# RaspberryPiSigfoxBoard.net
KiCad netlist of a schematic drawn in EAGLE
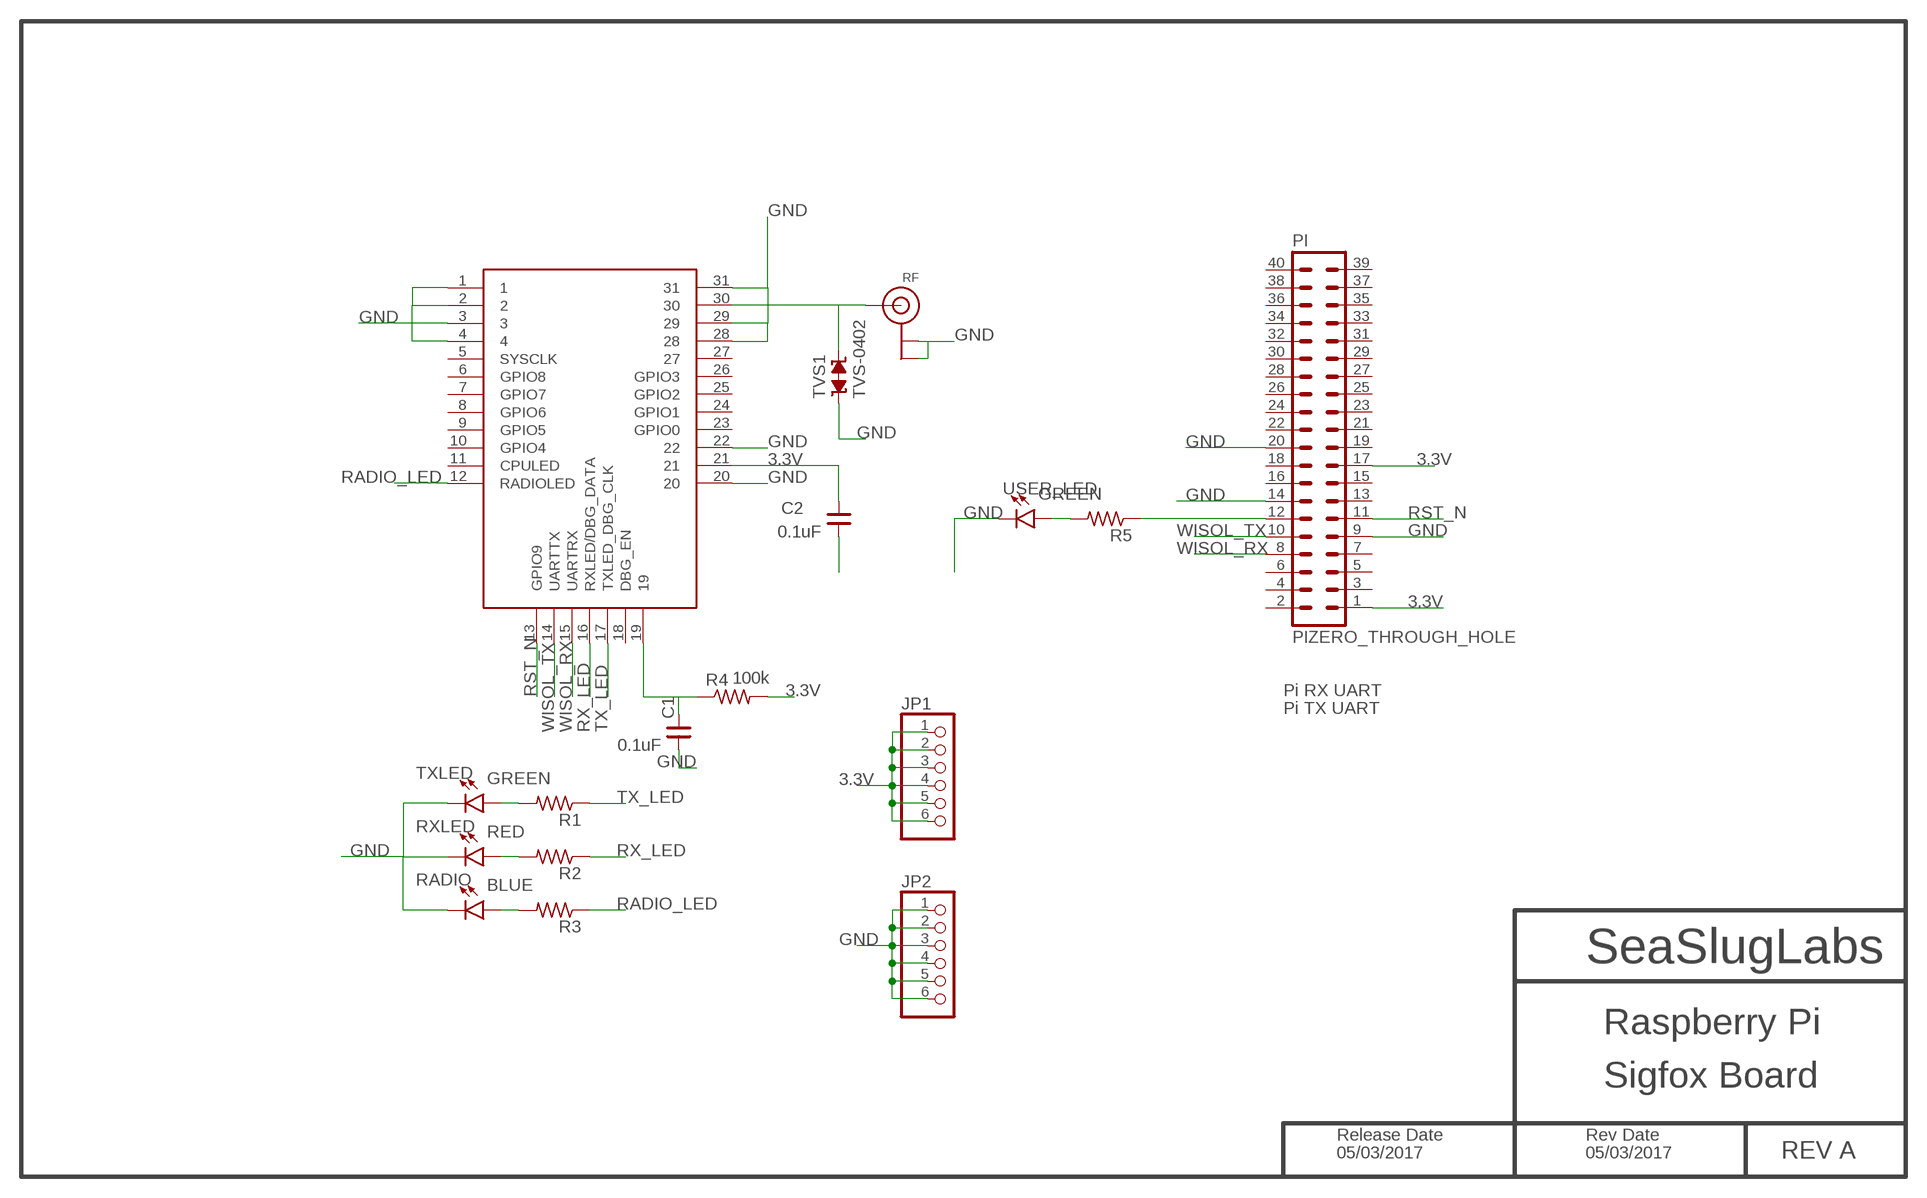
[diagram p0: schematic, sheet 1]

(export (version "E")
  (design (tool "Eeschema 10.0.6"))
  (components
    (comp (ref "C1")
      (value "0.1uF")
      (footprint "eagle-import:0402")
      (libsource (lib "eagle-import") (part "CNP-0402"))
    )
    (comp (ref "C2")
      (value "0.1uF")
      (footprint "eagle-import:0402")
      (libsource (lib "eagle-import") (part "CNP-0402"))
    )
    (comp (ref "JP1")
      (value "PINHD-1X6B")
      (footprint "eagle-import:1X06-BIG")
      (libsource (lib "eagle-import") (part "PINHD-1X6B"))
    )
    (comp (ref "JP2")
      (value "PINHD-1X6B")
      (footprint "eagle-import:1X06-BIG")
      (libsource (lib "eagle-import") (part "PINHD-1X6B"))
    )
    (comp (ref "PI")
      (value "PIZERO_THROUGH_HOLE")
      (footprint "eagle-import:PIZERO_THOUGH_HOLE")
      (libsource (lib "eagle-import") (part "PIZERO_THROUGH_HOLE"))
    )
    (comp (ref "R1")
      (value "R-US_R0402")
      (footprint "eagle-import:R0402")
      (libsource (lib "eagle-import") (part "R-US_R0402"))
    )
    (comp (ref "R2")
      (value "R-US_R0402")
      (footprint "eagle-import:R0402")
      (libsource (lib "eagle-import") (part "R-US_R0402"))
    )
    (comp (ref "R3")
      (value "R-US_R0402")
      (footprint "eagle-import:R0402")
      (libsource (lib "eagle-import") (part "R-US_R0402"))
    )
    (comp (ref "R4")
      (value "100k")
      (footprint "eagle-import:R0402")
      (libsource (lib "eagle-import") (part "R-US_R0402"))
    )
    (comp (ref "R5")
      (value "R-US_R0402")
      (footprint "eagle-import:R0402")
      (libsource (lib "eagle-import") (part "R-US_R0402"))
    )
    (comp (ref "RADIO")
      (value "BLUE")
      (footprint "eagle-import:LED-0603")
      (libsource (lib "eagle-import") (part "LED-BLUE0603"))
    )
    (comp (ref "RF")
      (value "ANTENNA_U.FL")
      (footprint "eagle-import:U.FL")
      (libsource (lib "eagle-import") (part "ANTENNA_U.FL"))
    )
    (comp (ref "RXLED")
      (value "RED")
      (footprint "eagle-import:LED-0603")
      (libsource (lib "eagle-import") (part "LED-RED0603"))
    )
    (comp (ref "TVS1")
      (value "TVS-0402")
      (footprint "eagle-import:TVS0402")
      (libsource (lib "eagle-import") (part "TVS-0402"))
    )
    (comp (ref "TXLED")
      (value "GREEN")
      (footprint "eagle-import:LED-0603")
      (libsource (lib "eagle-import") (part "LED-GREEN0603"))
    )
    (comp (ref "USER_LED")
      (value "GREEN")
      (footprint "eagle-import:LED-0603")
      (libsource (lib "eagle-import") (part "LED-GREEN0603"))
    )
    (comp (ref "WSSFM10R2")
      (value "WSSFM10R2/R4WSSFM10R2R4")
      (footprint "eagle-import:WISOL")
      (libsource (lib "eagle-import") (part "WSSFM10R2/R4WSSFM10R2R4"))
    )
  )
  (nets
    (net (code "1") (name "/3.3V") (class "Default")
      (node (ref "C2") (pin "2") (pinfunction "2_2") (pintype "passive"))
      (node (ref "JP1") (pin "1") (pinfunction "1_1") (pintype "passive"))
      (node (ref "JP1") (pin "2") (pinfunction "2_2") (pintype "passive"))
      (node (ref "JP1") (pin "3") (pinfunction "3_3") (pintype "passive"))
      (node (ref "JP1") (pin "4") (pinfunction "4_4") (pintype "passive"))
      (node (ref "JP1") (pin "5") (pinfunction "5_5") (pintype "passive"))
      (node (ref "JP1") (pin "6") (pinfunction "6_6") (pintype "passive"))
      (node (ref "PI") (pin "1") (pinfunction "1_1") (pintype "passive"))
      (node (ref "PI") (pin "17") (pinfunction "17_17") (pintype "passive"))
      (node (ref "R4") (pin "2") (pinfunction "2_2") (pintype "passive"))
      (node (ref "WSSFM10R2") (pin "21") (pinfunction "21_21") (pintype "bidirectional"))
    )
    (net (code "2") (name "/GND") (class "Default")
      (node (ref "C1") (pin "1") (pinfunction "1_1") (pintype "passive"))
      (node (ref "C2") (pin "1") (pinfunction "1_1") (pintype "passive"))
      (node (ref "JP2") (pin "1") (pinfunction "1_1") (pintype "passive"))
      (node (ref "JP2") (pin "2") (pinfunction "2_2") (pintype "passive"))
      (node (ref "JP2") (pin "3") (pinfunction "3_3") (pintype "passive"))
      (node (ref "JP2") (pin "4") (pinfunction "4_4") (pintype "passive"))
      (node (ref "JP2") (pin "5") (pinfunction "5_5") (pintype "passive"))
      (node (ref "JP2") (pin "6") (pinfunction "6_6") (pintype "passive"))
      (node (ref "PI") (pin "14") (pinfunction "14_14") (pintype "passive"))
      (node (ref "PI") (pin "20") (pinfunction "20_20") (pintype "passive"))
      (node (ref "PI") (pin "9") (pinfunction "9_9") (pintype "passive"))
      (node (ref "RADIO") (pin "C") (pinfunction "C_C") (pintype "passive"))
      (node (ref "RF") (pin "1") (pinfunction "GND_1") (pintype "passive"))
      (node (ref "RF") (pin "2") (pinfunction "GND_2") (pintype "passive"))
      (node (ref "RXLED") (pin "C") (pinfunction "C_C") (pintype "passive"))
      (node (ref "TVS1") (pin "1") (pinfunction "1_1") (pintype "passive"))
      (node (ref "TXLED") (pin "C") (pinfunction "C_C") (pintype "passive"))
      (node (ref "USER_LED") (pin "C") (pinfunction "C_C") (pintype "passive"))
      (node (ref "WSSFM10R2") (pin "1") (pinfunction "1_1") (pintype "bidirectional"))
      (node (ref "WSSFM10R2") (pin "2") (pinfunction "2_2") (pintype "bidirectional"))
      (node (ref "WSSFM10R2") (pin "20") (pinfunction "20_20") (pintype "bidirectional"))
      (node (ref "WSSFM10R2") (pin "22") (pinfunction "22_22") (pintype "bidirectional"))
      (node (ref "WSSFM10R2") (pin "28") (pinfunction "28_28") (pintype "bidirectional"))
      (node (ref "WSSFM10R2") (pin "29") (pinfunction "29_29") (pintype "bidirectional"))
      (node (ref "WSSFM10R2") (pin "3") (pinfunction "3_3") (pintype "bidirectional"))
      (node (ref "WSSFM10R2") (pin "31") (pinfunction "31_31") (pintype "bidirectional"))
      (node (ref "WSSFM10R2") (pin "4") (pinfunction "4_4") (pintype "bidirectional"))
    )
    (net (code "3") (name "/RADIO_LED") (class "Default")
      (node (ref "R3") (pin "1") (pinfunction "1_1") (pintype "passive"))
      (node (ref "WSSFM10R2") (pin "12") (pinfunction "RADIOLED_12") (pintype "bidirectional"))
    )
    (net (code "4") (name "/RST_N") (class "Default")
      (node (ref "PI") (pin "11") (pinfunction "11_11") (pintype "passive"))
      (node (ref "WSSFM10R2") (pin "13") (pinfunction "GPIO9_13") (pintype "bidirectional"))
    )
    (net (code "5") (name "/RX_LED") (class "Default")
      (node (ref "R2") (pin "1") (pinfunction "1_1") (pintype "passive"))
      (node (ref "WSSFM10R2") (pin "16") (pinfunction "RXLED/DBG_DATA_16") (pintype "bidirectional"))
    )
    (net (code "6") (name "/TX_LED") (class "Default")
      (node (ref "R1") (pin "1") (pinfunction "1_1") (pintype "passive"))
      (node (ref "WSSFM10R2") (pin "17") (pinfunction "TXLED_DBG_CLK_17") (pintype "bidirectional"))
    )
    (net (code "7") (name "/WISOL_RX") (class "Default")
      (node (ref "PI") (pin "8") (pinfunction "8_8") (pintype "passive"))
      (node (ref "WSSFM10R2") (pin "15") (pinfunction "UARTRX_15") (pintype "bidirectional"))
    )
    (net (code "8") (name "/WISOL_TX") (class "Default")
      (node (ref "PI") (pin "10") (pinfunction "10_10") (pintype "passive"))
      (node (ref "WSSFM10R2") (pin "14") (pinfunction "UARTTX_14") (pintype "bidirectional"))
    )
    (net (code "9") (name "Net-(C1-Pad2)") (class "Default")
      (node (ref "C1") (pin "2") (pinfunction "2_2") (pintype "passive"))
      (node (ref "R4") (pin "1") (pinfunction "1_1") (pintype "passive"))
      (node (ref "WSSFM10R2") (pin "19") (pinfunction "19_19") (pintype "bidirectional"))
    )
    (net (code "10") (name "Net-(PI-Pad12)") (class "Default")
      (node (ref "PI") (pin "12") (pinfunction "12_12") (pintype "passive"))
      (node (ref "R5") (pin "1") (pinfunction "1_1") (pintype "passive"))
    )
    (net (code "11") (name "Net-(R1-Pad2)") (class "Default")
      (node (ref "R1") (pin "2") (pinfunction "2_2") (pintype "passive"))
      (node (ref "TXLED") (pin "A") (pinfunction "A_A") (pintype "passive"))
    )
    (net (code "12") (name "Net-(R2-Pad2)") (class "Default")
      (node (ref "R2") (pin "2") (pinfunction "2_2") (pintype "passive"))
      (node (ref "RXLED") (pin "A") (pinfunction "A_A") (pintype "passive"))
    )
    (net (code "13") (name "Net-(R3-Pad2)") (class "Default")
      (node (ref "R3") (pin "2") (pinfunction "2_2") (pintype "passive"))
      (node (ref "RADIO") (pin "A") (pinfunction "A_A") (pintype "passive"))
    )
    (net (code "14") (name "Net-(R5-Pad2)") (class "Default")
      (node (ref "R5") (pin "2") (pinfunction "2_2") (pintype "passive"))
      (node (ref "USER_LED") (pin "A") (pinfunction "A_A") (pintype "passive"))
    )
    (net (code "15") (name "Net-(RF-SIGNAL)") (class "Default")
      (node (ref "RF") (pin "3") (pinfunction "SIGNAL_3") (pintype "passive"))
      (node (ref "TVS1") (pin "2") (pinfunction "2_2") (pintype "passive"))
      (node (ref "WSSFM10R2") (pin "30") (pinfunction "30_30") (pintype "bidirectional"))
    )
    (net (code "16") (name "unconnected-(PI-Pad2)") (class "Default")
      (node (ref "PI") (pin "2") (pinfunction "2_2") (pintype "passive"))
    )
    (net (code "17") (name "unconnected-(PI-Pad3)") (class "Default")
      (node (ref "PI") (pin "3") (pinfunction "3_3") (pintype "passive"))
    )
    (net (code "18") (name "unconnected-(PI-Pad4)") (class "Default")
      (node (ref "PI") (pin "4") (pinfunction "4_4") (pintype "passive"))
    )
    (net (code "19") (name "unconnected-(PI-Pad5)") (class "Default")
      (node (ref "PI") (pin "5") (pinfunction "5_5") (pintype "passive"))
    )
    (net (code "20") (name "unconnected-(PI-Pad6)") (class "Default")
      (node (ref "PI") (pin "6") (pinfunction "6_6") (pintype "passive"))
    )
    (net (code "21") (name "unconnected-(PI-Pad7)") (class "Default")
      (node (ref "PI") (pin "7") (pinfunction "7_7") (pintype "passive"))
    )
    (net (code "22") (name "unconnected-(PI-Pad13)") (class "Default")
      (node (ref "PI") (pin "13") (pinfunction "13_13") (pintype "passive"))
    )
    (net (code "23") (name "unconnected-(PI-Pad15)") (class "Default")
      (node (ref "PI") (pin "15") (pinfunction "15_15") (pintype "passive"))
    )
    (net (code "24") (name "unconnected-(PI-Pad16)") (class "Default")
      (node (ref "PI") (pin "16") (pinfunction "16_16") (pintype "passive"))
    )
    (net (code "25") (name "unconnected-(PI-Pad18)") (class "Default")
      (node (ref "PI") (pin "18") (pinfunction "18_18") (pintype "passive"))
    )
    (net (code "26") (name "unconnected-(PI-Pad19)") (class "Default")
      (node (ref "PI") (pin "19") (pinfunction "19_19") (pintype "passive"))
    )
    (net (code "27") (name "unconnected-(PI-Pad21)") (class "Default")
      (node (ref "PI") (pin "21") (pinfunction "21_21") (pintype "passive"))
    )
    (net (code "28") (name "unconnected-(PI-Pad22)") (class "Default")
      (node (ref "PI") (pin "22") (pinfunction "22_22") (pintype "passive"))
    )
    (net (code "29") (name "unconnected-(PI-Pad23)") (class "Default")
      (node (ref "PI") (pin "23") (pinfunction "23_23") (pintype "passive"))
    )
    (net (code "30") (name "unconnected-(PI-Pad24)") (class "Default")
      (node (ref "PI") (pin "24") (pinfunction "24_24") (pintype "passive"))
    )
    (net (code "31") (name "unconnected-(PI-Pad25)") (class "Default")
      (node (ref "PI") (pin "25") (pinfunction "25_25") (pintype "passive"))
    )
    (net (code "32") (name "unconnected-(PI-Pad26)") (class "Default")
      (node (ref "PI") (pin "26") (pinfunction "26_26") (pintype "passive"))
    )
    (net (code "33") (name "unconnected-(PI-Pad27)") (class "Default")
      (node (ref "PI") (pin "27") (pinfunction "27_27") (pintype "passive"))
    )
    (net (code "34") (name "unconnected-(PI-Pad28)") (class "Default")
      (node (ref "PI") (pin "28") (pinfunction "28_28") (pintype "passive"))
    )
    (net (code "35") (name "unconnected-(PI-Pad29)") (class "Default")
      (node (ref "PI") (pin "29") (pinfunction "29_29") (pintype "passive"))
    )
    (net (code "36") (name "unconnected-(PI-Pad30)") (class "Default")
      (node (ref "PI") (pin "30") (pinfunction "30_30") (pintype "passive"))
    )
    (net (code "37") (name "unconnected-(PI-Pad31)") (class "Default")
      (node (ref "PI") (pin "31") (pinfunction "31_31") (pintype "passive"))
    )
    (net (code "38") (name "unconnected-(PI-Pad32)") (class "Default")
      (node (ref "PI") (pin "32") (pinfunction "32_32") (pintype "passive"))
    )
    (net (code "39") (name "unconnected-(PI-Pad33)") (class "Default")
      (node (ref "PI") (pin "33") (pinfunction "33_33") (pintype "passive"))
    )
    (net (code "40") (name "unconnected-(PI-Pad34)") (class "Default")
      (node (ref "PI") (pin "34") (pinfunction "34_34") (pintype "passive"))
    )
    (net (code "41") (name "unconnected-(PI-Pad35)") (class "Default")
      (node (ref "PI") (pin "35") (pinfunction "35_35") (pintype "passive"))
    )
    (net (code "42") (name "unconnected-(PI-Pad36)") (class "Default")
      (node (ref "PI") (pin "36") (pinfunction "36_36") (pintype "passive"))
    )
    (net (code "43") (name "unconnected-(PI-Pad37)") (class "Default")
      (node (ref "PI") (pin "37") (pinfunction "37_37") (pintype "passive"))
    )
    (net (code "44") (name "unconnected-(PI-Pad38)") (class "Default")
      (node (ref "PI") (pin "38") (pinfunction "38_38") (pintype "passive"))
    )
    (net (code "45") (name "unconnected-(PI-Pad39)") (class "Default")
      (node (ref "PI") (pin "39") (pinfunction "39_39") (pintype "passive"))
    )
    (net (code "46") (name "unconnected-(PI-Pad40)") (class "Default")
      (node (ref "PI") (pin "40") (pinfunction "40_40") (pintype "passive"))
    )
    (net (code "47") (name "unconnected-(WSSFM10R2-CPULED-Pad11)") (class "Default")
      (node (ref "WSSFM10R2") (pin "11") (pinfunction "CPULED_11") (pintype "bidirectional"))
    )
    (net (code "48") (name "unconnected-(WSSFM10R2-DBG_EN-Pad18)") (class "Default")
      (node (ref "WSSFM10R2") (pin "18") (pinfunction "DBG_EN_18") (pintype "bidirectional"))
    )
    (net (code "49") (name "unconnected-(WSSFM10R2-GPIO0-Pad23)") (class "Default")
      (node (ref "WSSFM10R2") (pin "23") (pinfunction "GPIO0_23") (pintype "bidirectional"))
    )
    (net (code "50") (name "unconnected-(WSSFM10R2-GPIO1-Pad24)") (class "Default")
      (node (ref "WSSFM10R2") (pin "24") (pinfunction "GPIO1_24") (pintype "bidirectional"))
    )
    (net (code "51") (name "unconnected-(WSSFM10R2-GPIO2-Pad25)") (class "Default")
      (node (ref "WSSFM10R2") (pin "25") (pinfunction "GPIO2_25") (pintype "bidirectional"))
    )
    (net (code "52") (name "unconnected-(WSSFM10R2-GPIO3-Pad26)") (class "Default")
      (node (ref "WSSFM10R2") (pin "26") (pinfunction "GPIO3_26") (pintype "bidirectional"))
    )
    (net (code "53") (name "unconnected-(WSSFM10R2-GPIO4-Pad10)") (class "Default")
      (node (ref "WSSFM10R2") (pin "10") (pinfunction "GPIO4_10") (pintype "bidirectional"))
    )
    (net (code "54") (name "unconnected-(WSSFM10R2-GPIO5-Pad9)") (class "Default")
      (node (ref "WSSFM10R2") (pin "9") (pinfunction "GPIO5_9") (pintype "bidirectional"))
    )
    (net (code "55") (name "unconnected-(WSSFM10R2-GPIO6-Pad8)") (class "Default")
      (node (ref "WSSFM10R2") (pin "8") (pinfunction "GPIO6_8") (pintype "bidirectional"))
    )
    (net (code "56") (name "unconnected-(WSSFM10R2-GPIO7-Pad7)") (class "Default")
      (node (ref "WSSFM10R2") (pin "7") (pinfunction "GPIO7_7") (pintype "bidirectional"))
    )
    (net (code "57") (name "unconnected-(WSSFM10R2-GPIO8-Pad6)") (class "Default")
      (node (ref "WSSFM10R2") (pin "6") (pinfunction "GPIO8_6") (pintype "bidirectional"))
    )
    (net (code "58") (name "unconnected-(WSSFM10R2-Pad27)") (class "Default")
      (node (ref "WSSFM10R2") (pin "27") (pinfunction "27_27") (pintype "bidirectional"))
    )
    (net (code "59") (name "unconnected-(WSSFM10R2-SYSCLK-Pad5)") (class "Default")
      (node (ref "WSSFM10R2") (pin "5") (pinfunction "SYSCLK_5") (pintype "bidirectional"))
    )
  )
)
